# HDMI_OUTPUT_AD9389.net
KiCad netlist of a schematic drawn in Altium Designer
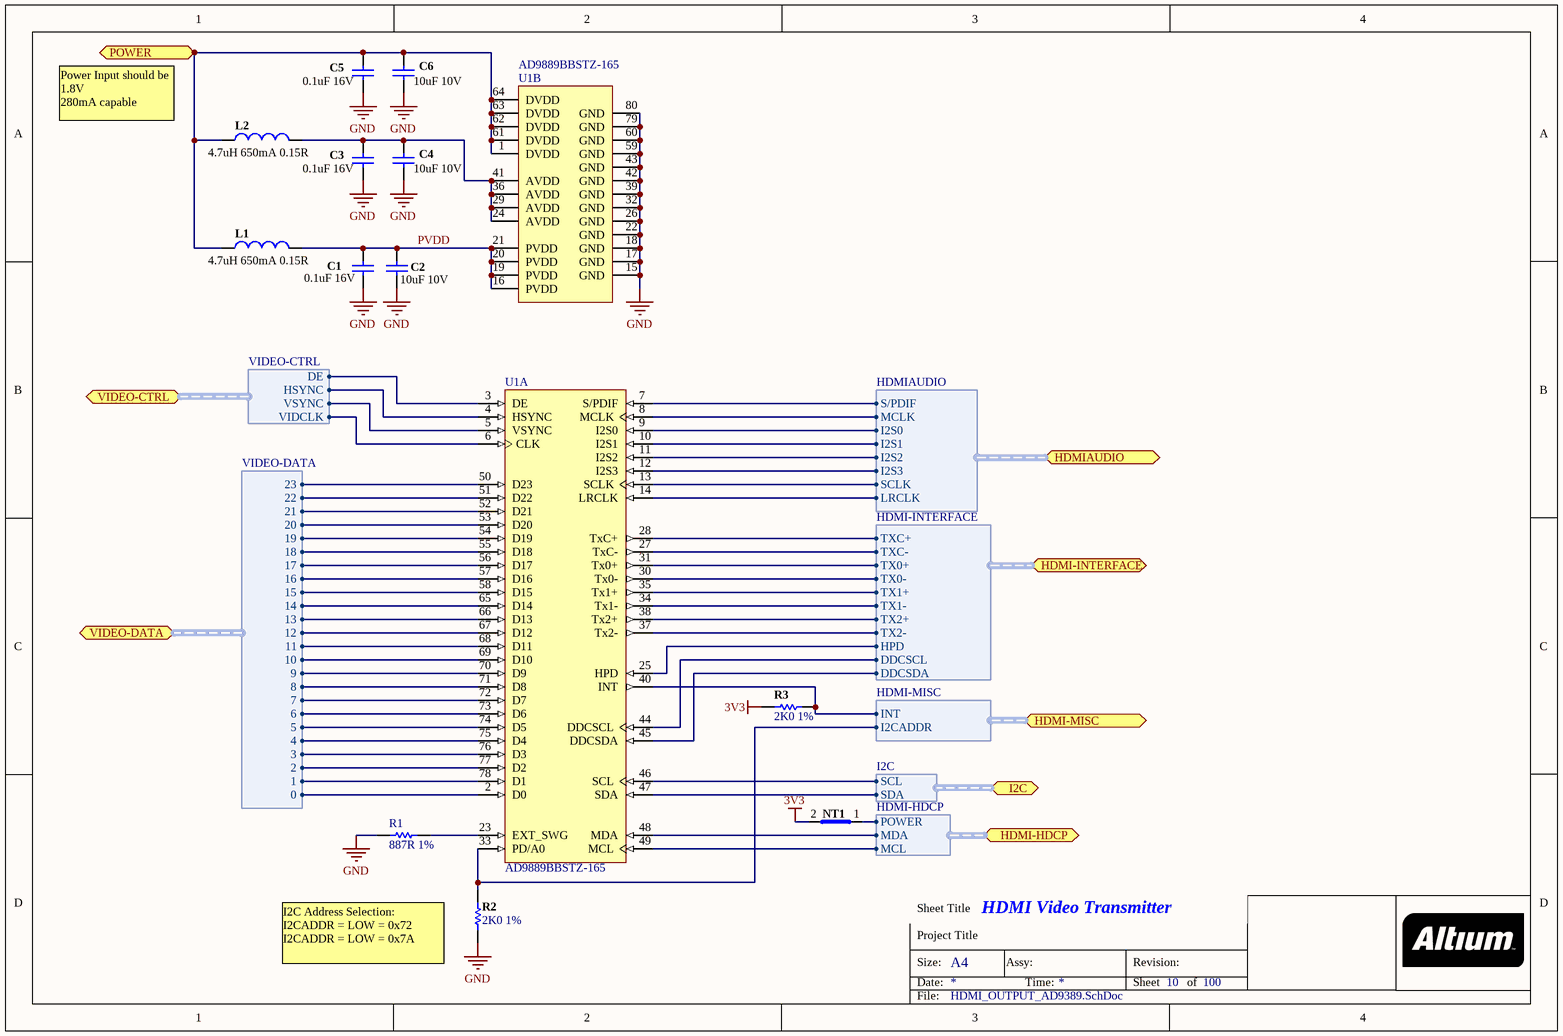
[diagram p0: HDMI_OUTPUT_AD9389.SchDoc]

(export (version "E")
  (design (tool "Eeschema 10.0.6"))
  (components
    (comp (ref "C1")
      (value "0.1uF 16V")
      (footprint "CAPC1005-STAR")
      (description "Capacitor, Ceramic, 0.1uF 10% 16V 0402 (1005) X7R")
      (fields (field (name "TOLERANCE") "10 %"))
      (libsource (lib "AltiumDesignLibrary") (part "CAP-NP"))
    )
    (comp (ref "C2")
      (value "10uF 10V")
      (footprint "CAPC2012-STAR")
      (description "Capacitor, Ceramic, 10uF 10% 10V 0805 (2012) X5R")
      (fields (field (name "TOLERANCE") "10 %"))
      (libsource (lib "AltiumDesignLibrary") (part "CAP-NP"))
    )
    (comp (ref "C3")
      (value "0.1uF 16V")
      (footprint "CAPC1005-STAR")
      (description "Capacitor, Ceramic, 0.1uF 10% 16V 0402 (1005) X7R")
      (fields (field (name "TOLERANCE") "10 %"))
      (libsource (lib "AltiumDesignLibrary") (part "CAP-NP"))
    )
    (comp (ref "C4")
      (value "10uF 10V")
      (footprint "CAPC2012-STAR")
      (description "Capacitor, Ceramic, 10uF 10% 10V 0805 (2012) X5R")
      (fields (field (name "TOLERANCE") "10 %"))
      (libsource (lib "AltiumDesignLibrary") (part "CAP-NP"))
    )
    (comp (ref "C5")
      (value "0.1uF 16V")
      (footprint "CAPC1005-STAR")
      (description "Capacitor, Ceramic, 0.1uF 10% 16V 0402 (1005) X7R")
      (fields (field (name "TOLERANCE") "10 %"))
      (libsource (lib "AltiumDesignLibrary") (part "CAP-NP"))
    )
    (comp (ref "C6")
      (value "10uF 10V")
      (footprint "CAPC2012-STAR")
      (description "Capacitor, Ceramic, 10uF 10% 10V 0805 (2012) X5R")
      (fields (field (name "TOLERANCE") "10 %"))
      (libsource (lib "AltiumDesignLibrary") (part "CAP-NP"))
    )
    (comp (ref "L1")
      (value "4.7uH 650mA 0.15R")
      (footprint "INDC3225")
      (description "Inductor, 4.7uH 650mA 0.15R 1210 (3225) LQH32CN4R7M11L")
      (libsource (lib "AltiumDesignLibrary") (part "IND"))
    )
    (comp (ref "L2")
      (value "4.7uH 650mA 0.15R")
      (footprint "INDC3225")
      (description "Inductor, 4.7uH 650mA 0.15R 1210 (3225) LQH32CN4R7M11L")
      (libsource (lib "AltiumDesignLibrary") (part "IND"))
    )
    (comp (ref "NT1")
      (value "Net Tie SMT2")
      (footprint "NETTIE-SMT2-31X39")
      (description "Net-Tie, Surface Mount, 2 x 2.0mm x 0.8mm SMT Pads - For 0.8mm Track")
      (libsource (lib "AltiumDesignLibrary") (part "NETTIE-SMT2"))
    )
    (comp (ref "R1")
      (value "887R 1%")
      (footprint "RESC1005-STAR")
      (description "Resistor, 887R 1% 0402 (1005)")
      (fields (field (name "TOLERANCE") "1 %"))
      (libsource (lib "AltiumDesignLibrary") (part "RES"))
    )
    (comp (ref "R2")
      (value "2K0 1%")
      (footprint "RESC1005-STAR")
      (description "Resistor, 2K0 1% 0402 (1005)")
      (fields (field (name "TOLERANCE") "1 %"))
      (libsource (lib "AltiumDesignLibrary") (part "RES"))
    )
    (comp (ref "R3")
      (value "2K0 1%")
      (footprint "RESC1005-STAR")
      (description "Resistor, 2K0 1% 0402 (1005)")
      (fields (field (name "TOLERANCE") "1 %"))
      (libsource (lib "AltiumDesignLibrary") (part "RES"))
    )
    (comp (ref "U1")
      (value "AD9889BBSTZ-165")
      (footprint "ST-80-2_V")
      (description "AD9889, HDMI Video Transmitter, TQFP")
      (libsource (lib "AltiumDesignLibrary") (part "AD9889BBSTZ-165"))
    )
  )
  (nets
    (net (code "8") (name "/0") (class "Default")
      (node (ref "U1") (pin "2") (pinfunction "D0_2") (pintype "input"))
    )
    (net (code "9") (name "/1") (class "Default")
      (node (ref "U1") (pin "78") (pinfunction "D1_78") (pintype "input"))
    )
    (net (code "10") (name "/2") (class "Default")
      (node (ref "U1") (pin "77") (pinfunction "D2_77") (pintype "input"))
    )
    (net (code "11") (name "/3") (class "Default")
      (node (ref "U1") (pin "76") (pinfunction "D3_76") (pintype "input"))
    )
    (net (code "12") (name "/4") (class "Default")
      (node (ref "U1") (pin "75") (pinfunction "D4_75") (pintype "input"))
    )
    (net (code "13") (name "/5") (class "Default")
      (node (ref "U1") (pin "74") (pinfunction "D5_74") (pintype "input"))
    )
    (net (code "14") (name "/6") (class "Default")
      (node (ref "U1") (pin "73") (pinfunction "D6_73") (pintype "input"))
    )
    (net (code "15") (name "/7") (class "Default")
      (node (ref "U1") (pin "72") (pinfunction "D7_72") (pintype "input"))
    )
    (net (code "16") (name "/8") (class "Default")
      (node (ref "U1") (pin "71") (pinfunction "D8_71") (pintype "input"))
    )
    (net (code "17") (name "/9") (class "Default")
      (node (ref "U1") (pin "70") (pinfunction "D9_70") (pintype "input"))
    )
    (net (code "18") (name "/10") (class "Default")
      (node (ref "U1") (pin "69") (pinfunction "D10_69") (pintype "input"))
    )
    (net (code "19") (name "/11") (class "Default")
      (node (ref "U1") (pin "68") (pinfunction "D11_68") (pintype "input"))
    )
    (net (code "20") (name "/12") (class "Default")
      (node (ref "U1") (pin "67") (pinfunction "D12_67") (pintype "input"))
    )
    (net (code "21") (name "/13") (class "Default")
      (node (ref "U1") (pin "66") (pinfunction "D13_66") (pintype "input"))
    )
    (net (code "22") (name "/14") (class "Default")
      (node (ref "U1") (pin "65") (pinfunction "D14_65") (pintype "input"))
    )
    (net (code "23") (name "/15") (class "Default")
      (node (ref "U1") (pin "58") (pinfunction "D15_58") (pintype "input"))
    )
    (net (code "24") (name "/16") (class "Default")
      (node (ref "U1") (pin "57") (pinfunction "D16_57") (pintype "input"))
    )
    (net (code "25") (name "/17") (class "Default")
      (node (ref "U1") (pin "56") (pinfunction "D17_56") (pintype "input"))
    )
    (net (code "26") (name "/18") (class "Default")
      (node (ref "U1") (pin "55") (pinfunction "D18_55") (pintype "input"))
    )
    (net (code "27") (name "/19") (class "Default")
      (node (ref "U1") (pin "54") (pinfunction "D19_54") (pintype "input"))
    )
    (net (code "28") (name "/20") (class "Default")
      (node (ref "U1") (pin "53") (pinfunction "D20_53") (pintype "input"))
    )
    (net (code "29") (name "/21") (class "Default")
      (node (ref "U1") (pin "52") (pinfunction "D21_52") (pintype "input"))
    )
    (net (code "30") (name "/22") (class "Default")
      (node (ref "U1") (pin "51") (pinfunction "D22_51") (pintype "input"))
    )
    (net (code "31") (name "/23") (class "Default")
      (node (ref "U1") (pin "50") (pinfunction "D23_50") (pintype "input"))
    )
    (net (code "32") (name "/DDCSCL") (class "Default")
      (node (ref "U1") (pin "44") (pinfunction "DDCSCL_44") (pintype "input"))
    )
    (net (code "33") (name "/DDCSDA") (class "Default")
      (node (ref "U1") (pin "45") (pinfunction "DDCSDA_45") (pintype "input"))
    )
    (net (code "34") (name "/DE") (class "Default")
      (node (ref "U1") (pin "3") (pinfunction "DE_3") (pintype "input"))
    )
    (net (code "35") (name "/HPD") (class "Default")
      (node (ref "U1") (pin "25") (pinfunction "HPD_25") (pintype "input"))
    )
    (net (code "36") (name "/HSYNC") (class "Default")
      (node (ref "U1") (pin "4") (pinfunction "HSYNC_4") (pintype "input"))
    )
    (net (code "37") (name "/I2CADDR") (class "Default")
      (node (ref "R2") (pin "1") (pinfunction "1_1") (pintype "passive"))
      (node (ref "U1") (pin "33") (pinfunction "PD/A0_33") (pintype "input"))
    )
    (net (code "38") (name "/I2S0") (class "Default")
      (node (ref "U1") (pin "9") (pinfunction "I2S0_9") (pintype "input"))
    )
    (net (code "39") (name "/I2S1") (class "Default")
      (node (ref "U1") (pin "10") (pinfunction "I2S1_10") (pintype "input"))
    )
    (net (code "40") (name "/I2S2") (class "Default")
      (node (ref "U1") (pin "11") (pinfunction "I2S2_11") (pintype "input"))
    )
    (net (code "41") (name "/I2S3") (class "Default")
      (node (ref "U1") (pin "12") (pinfunction "I2S3_12") (pintype "input"))
    )
    (net (code "42") (name "/INT") (class "Default")
      (node (ref "R3") (pin "2") (pinfunction "2_2") (pintype "passive"))
      (node (ref "U1") (pin "40") (pinfunction "INT_40") (pintype "output"))
    )
    (net (code "43") (name "/LRCLK") (class "Default")
      (node (ref "U1") (pin "14") (pinfunction "LRCLK_14") (pintype "input"))
    )
    (net (code "44") (name "/MCL") (class "Default")
      (node (ref "U1") (pin "49") (pinfunction "MCL_49") (pintype "input"))
    )
    (net (code "45") (name "/MCLK") (class "Default")
      (node (ref "U1") (pin "8") (pinfunction "MCLK_8") (pintype "input"))
    )
    (net (code "46") (name "/MDA") (class "Default")
      (node (ref "U1") (pin "48") (pinfunction "MDA_48") (pintype "input"))
    )
    (net (code "47") (name "/POWER") (class "Default")
      (node (ref "C5") (pin "1") (pinfunction "1_1") (pintype "passive"))
      (node (ref "C6") (pin "1") (pinfunction "1_1") (pintype "passive"))
      (node (ref "L1") (pin "1") (pinfunction "1_1") (pintype "passive"))
      (node (ref "L2") (pin "1") (pinfunction "1_1") (pintype "passive"))
      (node (ref "U1") (pin "1") (pinfunction "DVDD_1") (pintype "power_in"))
      (node (ref "U1") (pin "61") (pinfunction "DVDD_61") (pintype "power_in"))
      (node (ref "U1") (pin "62") (pinfunction "DVDD_62") (pintype "power_in"))
      (node (ref "U1") (pin "63") (pinfunction "DVDD_63") (pintype "power_in"))
      (node (ref "U1") (pin "64") (pinfunction "DVDD_64") (pintype "power_in"))
    )
    (net (code "48") (name "/PVDD") (class "Default")
      (node (ref "C1") (pin "1") (pinfunction "1_1") (pintype "passive"))
      (node (ref "C2") (pin "1") (pinfunction "1_1") (pintype "passive"))
      (node (ref "L1") (pin "2") (pinfunction "2_2") (pintype "passive"))
      (node (ref "U1") (pin "16") (pinfunction "PVDD_16") (pintype "power_in"))
      (node (ref "U1") (pin "19") (pinfunction "PVDD_19") (pintype "power_in"))
      (node (ref "U1") (pin "20") (pinfunction "PVDD_20") (pintype "power_in"))
      (node (ref "U1") (pin "21") (pinfunction "PVDD_21") (pintype "power_in"))
    )
    (net (code "49") (name "/SCL") (class "Default")
      (node (ref "U1") (pin "46") (pinfunction "SCL_46") (pintype "input"))
    )
    (net (code "50") (name "/SCLK") (class "Default")
      (node (ref "U1") (pin "13") (pinfunction "SCLK_13") (pintype "input"))
    )
    (net (code "51") (name "/SDA") (class "Default")
      (node (ref "U1") (pin "47") (pinfunction "SDA_47") (pintype "input"))
    )
    (net (code "52") (name "/S{slash}PDIF") (class "Default")
      (node (ref "U1") (pin "7") (pinfunction "S/PDIF_7") (pintype "input"))
    )
    (net (code "53") (name "/TX0+") (class "Default")
      (node (ref "U1") (pin "31") (pinfunction "Tx0+_31") (pintype "output"))
    )
    (net (code "54") (name "/TX0-") (class "Default")
      (node (ref "U1") (pin "30") (pinfunction "Tx0-_30") (pintype "output"))
    )
    (net (code "55") (name "/TX1+") (class "Default")
      (node (ref "U1") (pin "35") (pinfunction "Tx1+_35") (pintype "output"))
    )
    (net (code "56") (name "/TX1-") (class "Default")
      (node (ref "U1") (pin "34") (pinfunction "Tx1-_34") (pintype "output"))
    )
    (net (code "57") (name "/TX2+") (class "Default")
      (node (ref "U1") (pin "38") (pinfunction "Tx2+_38") (pintype "output"))
    )
    (net (code "58") (name "/TX2-") (class "Default")
      (node (ref "U1") (pin "37") (pinfunction "Tx2-_37") (pintype "output"))
    )
    (net (code "59") (name "/TXC+") (class "Default")
      (node (ref "U1") (pin "28") (pinfunction "TxC+_28") (pintype "output"))
    )
    (net (code "60") (name "/TXC-") (class "Default")
      (node (ref "U1") (pin "27") (pinfunction "TxC-_27") (pintype "output"))
    )
    (net (code "61") (name "/VIDCLK") (class "Default")
      (node (ref "U1") (pin "6") (pinfunction "CLK_6") (pintype "input"))
    )
    (net (code "62") (name "/VSYNC") (class "Default")
      (node (ref "U1") (pin "5") (pinfunction "VSYNC_5") (pintype "input"))
    )
    (net (code "70") (name "3V3") (class "Default")
      (node (ref "NT1") (pin "2") (pinfunction "Net2_2") (pintype "passive"))
      (node (ref "R3") (pin "1") (pinfunction "1_1") (pintype "passive"))
    )
    (net (code "71") (name "GND") (class "Default")
      (node (ref "C1") (pin "2") (pinfunction "2_2") (pintype "passive"))
      (node (ref "C2") (pin "2") (pinfunction "2_2") (pintype "passive"))
      (node (ref "C3") (pin "2") (pinfunction "2_2") (pintype "passive"))
      (node (ref "C4") (pin "2") (pinfunction "2_2") (pintype "passive"))
      (node (ref "C5") (pin "2") (pinfunction "2_2") (pintype "passive"))
      (node (ref "C6") (pin "2") (pinfunction "2_2") (pintype "passive"))
      (node (ref "R1") (pin "1") (pinfunction "1_1") (pintype "passive"))
      (node (ref "R2") (pin "2") (pinfunction "2_2") (pintype "passive"))
      (node (ref "U1") (pin "15") (pinfunction "GND_15") (pintype "power_in"))
      (node (ref "U1") (pin "17") (pinfunction "GND_17") (pintype "power_in"))
      (node (ref "U1") (pin "18") (pinfunction "GND_18") (pintype "power_in"))
      (node (ref "U1") (pin "22") (pinfunction "GND_22") (pintype "power_in"))
      (node (ref "U1") (pin "26") (pinfunction "GND_26") (pintype "power_in"))
      (node (ref "U1") (pin "32") (pinfunction "GND_32") (pintype "power_in"))
      (node (ref "U1") (pin "39") (pinfunction "GND_39") (pintype "power_in"))
      (node (ref "U1") (pin "42") (pinfunction "GND_42") (pintype "power_in"))
      (node (ref "U1") (pin "43") (pinfunction "GND_43") (pintype "power_in"))
      (node (ref "U1") (pin "59") (pinfunction "GND_59") (pintype "power_in"))
      (node (ref "U1") (pin "60") (pinfunction "GND_60") (pintype "power_in"))
      (node (ref "U1") (pin "79") (pinfunction "GND_79") (pintype "power_in"))
      (node (ref "U1") (pin "80") (pinfunction "GND_80") (pintype "power_in"))
    )
    (net (code "72") (name "Net-(C3-Pad1)") (class "Default")
      (node (ref "C3") (pin "1") (pinfunction "1_1") (pintype "passive"))
      (node (ref "C4") (pin "1") (pinfunction "1_1") (pintype "passive"))
      (node (ref "L2") (pin "2") (pinfunction "2_2") (pintype "passive"))
      (node (ref "U1") (pin "24") (pinfunction "AVDD_24") (pintype "power_in"))
      (node (ref "U1") (pin "29") (pinfunction "AVDD_29") (pintype "power_in"))
      (node (ref "U1") (pin "36") (pinfunction "AVDD_36") (pintype "power_in"))
      (node (ref "U1") (pin "41") (pinfunction "AVDD_41") (pintype "power_in"))
    )
    (net (code "73") (name "Net-(U1A-EXT_SWG)") (class "Default")
      (node (ref "R1") (pin "2") (pinfunction "2_2") (pintype "passive"))
      (node (ref "U1") (pin "23") (pinfunction "EXT_SWG_23") (pintype "input"))
    )
    (net (code "74") (name "unconnected-(NT1-Net1-Pad1)") (class "Default")
      (node (ref "NT1") (pin "1") (pinfunction "Net1_1") (pintype "passive"))
    )
  )
)
